# PCB_schematic.net
KiCad netlist of a schematic drawn in Altium Designer
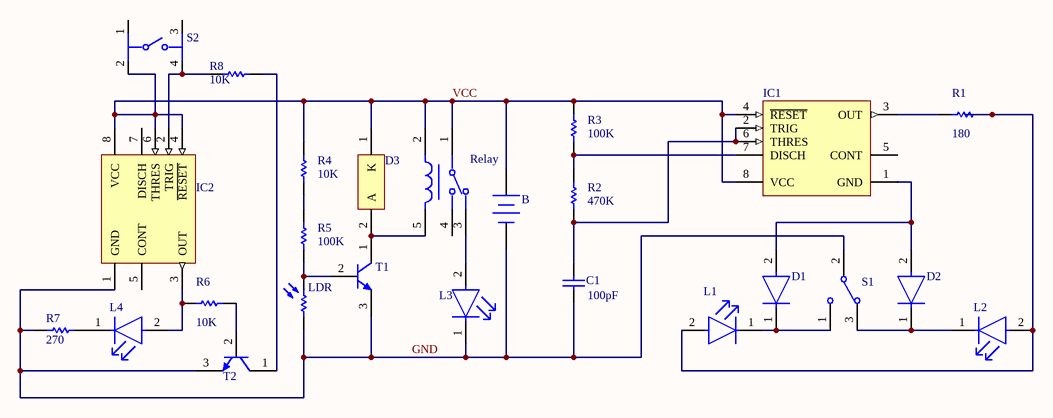
[diagram p0: PCB_schematic.SchDoc]

(export (version "E")
  (design (tool "Eeschema 10.0.6"))
  (components
    (comp (ref "B")
      (value "Battery")
      (footprint "BAT-2")
      (description "Multicell Battery")
      (fields (field (name "PUBLISHER") "Altium Limited"))
      (libsource (lib "Miscellaneous Devices") (part "Battery"))
    )
    (comp (ref "C1")
      (value "100pF")
      (footprint "RAD-0.3")
      (description "Capacitor")
      (fields (field (name "Comment") "Cap") (field (name "PUBLISHER") "Altium Limited"))
      (libsource (lib "Miscellaneous Devices") (part "Cap"))
    )
    (comp (ref "D1")
      (value "1N4007-E3/54")
      (footprint "FP-1N4007-MFG")
      (description "DIODE GEN PURP 1KV 1A DO204AL")
      (fields
        (field (name "OCTOPART") "https://octopart.com/1n4007-e3%2F54-vishay-39548207")
        (field (name "MANUFACTURER") "Vishay")
      )
      (libsource (lib "Altium Content Vault") (part "d7152d700b627762746794eb795d46e"))
    )
    (comp (ref "D2")
      (value "1N4007-E3/54")
      (footprint "FP-1N4007-MFG")
      (description "DIODE GEN PURP 1KV 1A DO204AL")
      (fields
        (field (name "OCTOPART") "https://octopart.com/1n4007-e3%2F54-vishay-39548207")
        (field (name "MANUFACTURER") "Vishay")
      )
      (libsource (lib "Altium Content Vault") (part "d7152d700b627762746794eb795d46e"))
    )
    (comp (ref "D3")
      (value "1N4001")
      (footprint "ONSC-AXIAL_LEAD-2-59-10_P")
      (description "Standard Recovery Rectifier, 2-Pin Axial_Lead, Pb-Free, Bulk Bag")
      (fields (field (name "MANUFACTURER") "On Semiconductor"))
      (libsource (lib "Altium Content Vault") (part "ONSC-D-K1A2-2_A"))
    )
    (comp (ref "IC1")
      (value "NE555P")
      (footprint "P0008A")
      (description "Precision Timer, 4.5 to 16 V, 0 to 70 degC, 8-Pin DIP, Pb-Free, Tube")
      (fields (field (name "MANUFACTURER") "TexasInstruments"))
      (libsource (lib "") (part "TI-NE555-P8_1"))
    )
    (comp (ref "IC2")
      (value "NE555P")
      (footprint "P0008A")
      (description "Precision Timer, 4.5 to 16 V, 0 to 70 degC, 8-Pin DIP, Pb-Free, Tube")
      (fields (field (name "MANUFACTURER") "TexasInstruments"))
      (libsource (lib "Altium Content Vault") (part "TI-NE555-P8"))
    )
    (comp (ref "L1")
      (value "HLMP-1719")
      (footprint "FP-HLMP-1719-MFG")
      (description "LED Uni-Color Yellow 2-Pin T-1")
      (fields (field (name "MANUFACTURER") "Broadcom"))
      (libsource (lib "Altium Content Vault") (part "8706943c75ba83719d021d2fdc84c58"))
    )
    (comp (ref "L2")
      (value "HLMP-1719")
      (footprint "FP-HLMP-1719-MFG")
      (description "LED Uni-Color Yellow 2-Pin T-1")
      (fields (field (name "MANUFACTURER") "Broadcom"))
      (libsource (lib "Altium Content Vault") (part "8706943c75ba83719d021d2fdc84c58"))
    )
    (comp (ref "L3")
      (value "HLMP-1719")
      (footprint "FP-HLMP-1719-MFG")
      (description "LED Uni-Color Yellow 2-Pin T-1")
      (fields (field (name "MANUFACTURER") "Broadcom"))
      (libsource (lib "Altium Content Vault") (part "8706943c75ba83719d021d2fdc84c58"))
    )
    (comp (ref "L4")
      (value "HLMP-1719")
      (footprint "FP-HLMP-1719-MFG")
      (description "LED Uni-Color Yellow 2-Pin T-1")
      (fields (field (name "MANUFACTURER") "Broadcom"))
      (libsource (lib "Altium Content Vault") (part "8706943c75ba83719d021d2fdc84c58"))
    )
    (comp (ref "LDR")
      (value "VT90N1")
      (footprint "EXCE-VT90N1")
      (description "Photoconductive Resistor, 200 kOhm, 100 V, 80 mW, -40 to 75 degC, 2-Pin THD, RoHS")
      (fields (field (name "MANUFACTURER") "Excelitas Technology"))
      (libsource (lib "Altium Content Vault") (part "PHOTO-RES-2"))
    )
    (comp (ref "R1")
      (value "180")
      (footprint "AXIAL-0.3")
      (description "Resistor")
      (fields (field (name "Comment") "Res1") (field (name "PUBLISHER") "Altium Limited"))
      (libsource (lib "Miscellaneous Devices") (part "Res1"))
    )
    (comp (ref "R2")
      (value "470K")
      (footprint "AXIAL-0.3")
      (description "Resistor")
      (fields (field (name "Comment") "Res1") (field (name "PUBLISHER") "Altium Limited"))
      (libsource (lib "Miscellaneous Devices") (part "Res1"))
    )
    (comp (ref "R3")
      (value "100K")
      (footprint "AXIAL-0.3")
      (description "Resistor")
      (fields (field (name "Comment") "Res1") (field (name "PUBLISHER") "Altium Limited"))
      (libsource (lib "Miscellaneous Devices") (part "Res1"))
    )
    (comp (ref "R4")
      (value "10K")
      (footprint "AXIAL-0.3")
      (description "Resistor")
      (fields (field (name "Comment") "Res1") (field (name "PUBLISHER") "Altium Limited"))
      (libsource (lib "Miscellaneous Devices") (part "Res1"))
    )
    (comp (ref "R5")
      (value "100K")
      (footprint "AXIAL-0.3")
      (description "Resistor")
      (fields (field (name "Comment") "Res1") (field (name "PUBLISHER") "Altium Limited"))
      (libsource (lib "Miscellaneous Devices") (part "Res1"))
    )
    (comp (ref "R6")
      (value "10K")
      (footprint "AXIAL-0.3")
      (description "Resistor")
      (fields (field (name "Comment") "Res1") (field (name "PUBLISHER") "Altium Limited"))
      (libsource (lib "Miscellaneous Devices") (part "Res1"))
    )
    (comp (ref "R7")
      (value "270")
      (footprint "AXIAL-0.3")
      (description "Resistor")
      (fields (field (name "Comment") "Res1") (field (name "PUBLISHER") "Altium Limited"))
      (libsource (lib "Miscellaneous Devices") (part "Res1"))
    )
    (comp (ref "R8")
      (value "10K")
      (footprint "AXIAL-0.3")
      (description "Resistor")
      (fields (field (name "Comment") "Res1") (field (name "PUBLISHER") "Altium Limited"))
      (libsource (lib "Miscellaneous Devices") (part "Res1"))
    )
    (comp (ref "Relay")
      (value "JS1F-12V-F")
      (footprint "FP-JS1F-12V-F-MFG")
      (description "RELAY GEN PURPOSE SPDT 10A 12V")
      (libsource (lib "Altium Content Vault") (part "ff81c261b07bbb1a4e05c84e23c1c37"))
    )
    (comp (ref "S1")
      (value "SW-SPDT")
      (footprint "TL36WW15050")
      (description "SPDT Subminiature Toggle Switch, Right Angle Mounting, Vertical Actuation")
      (fields (field (name "PUBLISHER") "Altium Limited"))
      (libsource (lib "Miscellaneous Devices") (part "SW-SPDT"))
    )
    (comp (ref "S2")
      (value "3-1825910-1")
      (footprint "FP-3-1825910-1-MFG")
      (description "SWITCH TACTILE SPST-NO 0.05A 24V")
      (fields
        (field (name "MANUFACTURER") "TE Connectivity")
        (field (name "OCTOPART") "https://octopart.com/3-1825910-1-te+connectivity-46506874")
      )
      (libsource (lib "Altium Content Vault") (part "b8895f3f4cefb76e1819d2863dba89b"))
    )
    (comp (ref "T1")
      (value "BC547B")
      (footprint "ONSC-TO-92-3-29-11")
      (description "Amplifier Transistor, NPN Silicon, 3-Pin TO-92, Bulk Box")
      (fields (field (name "MANUFACTURER") "On Semiconductor"))
      (libsource (lib "Altium Content Vault") (part "ONSC-NPN-C1B2E3-3"))
    )
    (comp (ref "T2")
      (value "BC547B")
      (footprint "ONSC-TO-92-3-29-11")
      (description "Amplifier Transistor, NPN Silicon, 3-Pin TO-92, Bulk Box")
      (fields (field (name "MANUFACTURER") "On Semiconductor"))
      (libsource (lib "Altium Content Vault") (part "ONSC-NPN-C1B2E3-3"))
    )
  )
  (nets
    (net (code "1") (name "/GND") (class "Default")
      (node (ref "B") (pin "2") (pinfunction "-_2") (pintype "passive"))
      (node (ref "C1") (pin "1") (pinfunction "1_1") (pintype "passive"))
      (node (ref "IC2") (pin "1") (pinfunction "GND_1") (pintype "power_in"))
      (node (ref "L3") (pin "1") (pinfunction "C_1") (pintype "passive"))
      (node (ref "LDR") (pin "1") (pinfunction "1_1") (pintype "passive"))
      (node (ref "R7") (pin "1") (pinfunction "1_1") (pintype "passive"))
      (node (ref "S1") (pin "2") (pinfunction "2_2") (pintype "passive"))
      (node (ref "T1") (pin "3") (pinfunction "E_3") (pintype "passive"))
      (node (ref "T2") (pin "3") (pinfunction "E_3") (pintype "passive"))
    )
    (net (code "2") (name "/VCC") (class "Default")
      (node (ref "B") (pin "1") (pinfunction "+_1") (pintype "passive"))
      (node (ref "D3") (pin "1") (pinfunction "K_1") (pintype "passive"))
      (node (ref "IC1") (pin "4") (pinfunction "~{RESET}_4") (pintype "input"))
      (node (ref "IC1") (pin "8") (pinfunction "VCC_8") (pintype "power_in"))
      (node (ref "IC2") (pin "4") (pinfunction "~{RESET}_4") (pintype "input"))
      (node (ref "IC2") (pin "6") (pinfunction "THRES_6") (pintype "input"))
      (node (ref "IC2") (pin "8") (pinfunction "VCC_8") (pintype "power_in"))
      (node (ref "R3") (pin "2") (pinfunction "2_2") (pintype "passive"))
      (node (ref "R4") (pin "2") (pinfunction "2_2") (pintype "passive"))
      (node (ref "Relay") (pin "1") (pinfunction "COM_1") (pintype "passive"))
      (node (ref "Relay") (pin "2") (pinfunction "2_2") (pintype "passive"))
      (node (ref "S2") (pin "2") (pinfunction "2_2") (pintype "passive"))
    )
    (net (code "3") (name "Net-(D1-A)") (class "Default")
      (node (ref "D1") (pin "2") (pinfunction "A_2") (pintype "passive"))
      (node (ref "D2") (pin "2") (pinfunction "A_2") (pintype "passive"))
      (node (ref "IC1") (pin "1") (pinfunction "GND_1") (pintype "power_in"))
    )
    (net (code "4") (name "Net-(D1-C)") (class "Default")
      (node (ref "D1") (pin "1") (pinfunction "C_1") (pintype "passive"))
      (node (ref "L1") (pin "1") (pinfunction "C_1") (pintype "passive"))
      (node (ref "S1") (pin "1") (pinfunction "1_1") (pintype "passive"))
    )
    (net (code "5") (name "Net-(D2-C)") (class "Default")
      (node (ref "D2") (pin "1") (pinfunction "C_1") (pintype "passive"))
      (node (ref "L2") (pin "1") (pinfunction "C_1") (pintype "passive"))
      (node (ref "S1") (pin "3") (pinfunction "3_3") (pintype "passive"))
    )
    (net (code "6") (name "Net-(D3-A)") (class "Default")
      (node (ref "D3") (pin "2") (pinfunction "A_2") (pintype "passive"))
      (node (ref "Relay") (pin "5") (pinfunction "5_5") (pintype "passive"))
      (node (ref "T1") (pin "1") (pinfunction "C_1") (pintype "passive"))
    )
    (net (code "7") (name "Net-(IC1-DISCH)") (class "Default")
      (node (ref "IC1") (pin "7") (pinfunction "DISCH_7") (pintype "open_collector"))
      (node (ref "R2") (pin "2") (pinfunction "2_2") (pintype "passive"))
      (node (ref "R3") (pin "1") (pinfunction "1_1") (pintype "passive"))
    )
    (net (code "8") (name "Net-(IC1-OUT)") (class "Default")
      (node (ref "IC1") (pin "3") (pinfunction "OUT_3") (pintype "output"))
      (node (ref "R1") (pin "2") (pinfunction "2_2") (pintype "passive"))
    )
    (net (code "9") (name "Net-(IC1-THRES)") (class "Default")
      (node (ref "C1") (pin "2") (pinfunction "2_2") (pintype "passive"))
      (node (ref "IC1") (pin "2") (pinfunction "TRIG_2") (pintype "input"))
      (node (ref "IC1") (pin "6") (pinfunction "THRES_6") (pintype "input"))
      (node (ref "R2") (pin "1") (pinfunction "1_1") (pintype "passive"))
    )
    (net (code "10") (name "Net-(IC2-OUT)") (class "Default")
      (node (ref "IC2") (pin "3") (pinfunction "OUT_3") (pintype "output"))
      (node (ref "L4") (pin "2") (pinfunction "A_2") (pintype "passive"))
      (node (ref "R6") (pin "1") (pinfunction "1_1") (pintype "passive"))
    )
    (net (code "11") (name "Net-(IC2-TRIG)") (class "Default")
      (node (ref "IC2") (pin "2") (pinfunction "TRIG_2") (pintype "input"))
      (node (ref "R8") (pin "1") (pinfunction "1_1") (pintype "passive"))
      (node (ref "S2") (pin "4") (pinfunction "4_4") (pintype "passive"))
    )
    (net (code "12") (name "Net-(L1-A)") (class "Default")
      (node (ref "L1") (pin "2") (pinfunction "A_2") (pintype "passive"))
      (node (ref "L2") (pin "2") (pinfunction "A_2") (pintype "passive"))
      (node (ref "R1") (pin "1") (pinfunction "1_1") (pintype "passive"))
    )
    (net (code "13") (name "Net-(L3-A)") (class "Default")
      (node (ref "L3") (pin "2") (pinfunction "A_2") (pintype "passive"))
      (node (ref "Relay") (pin "3") (pinfunction "NO_3") (pintype "passive"))
    )
    (net (code "14") (name "Net-(L4-C)") (class "Default")
      (node (ref "L4") (pin "1") (pinfunction "C_1") (pintype "passive"))
      (node (ref "R7") (pin "2") (pinfunction "2_2") (pintype "passive"))
    )
    (net (code "15") (name "Net-(R4-Pad1)") (class "Default")
      (node (ref "R4") (pin "1") (pinfunction "1_1") (pintype "passive"))
      (node (ref "R5") (pin "2") (pinfunction "2_2") (pintype "passive"))
    )
    (net (code "16") (name "Net-(T1-B)") (class "Default")
      (node (ref "LDR") (pin "2") (pinfunction "2_2") (pintype "passive"))
      (node (ref "R5") (pin "1") (pinfunction "1_1") (pintype "passive"))
      (node (ref "T1") (pin "2") (pinfunction "B_2") (pintype "passive"))
    )
    (net (code "17") (name "Net-(T2-B)") (class "Default")
      (node (ref "R6") (pin "2") (pinfunction "2_2") (pintype "passive"))
      (node (ref "T2") (pin "2") (pinfunction "B_2") (pintype "passive"))
    )
    (net (code "18") (name "Net-(T2-C)") (class "Default")
      (node (ref "R8") (pin "2") (pinfunction "2_2") (pintype "passive"))
      (node (ref "T2") (pin "1") (pinfunction "C_1") (pintype "passive"))
    )
    (net (code "19") (name "unconnected-(IC1-CONT-Pad5)") (class "Default")
      (node (ref "IC1") (pin "5") (pinfunction "CONT_5") (pintype "passive"))
    )
    (net (code "20") (name "unconnected-(IC2-CONT-Pad5)") (class "Default")
      (node (ref "IC2") (pin "5") (pinfunction "CONT_5") (pintype "passive"))
    )
    (net (code "21") (name "unconnected-(IC2-DISCH-Pad7)") (class "Default")
      (node (ref "IC2") (pin "7") (pinfunction "DISCH_7") (pintype "open_collector"))
    )
    (net (code "22") (name "unconnected-(Relay-NC-Pad4)") (class "Default")
      (node (ref "Relay") (pin "4") (pinfunction "NC_4") (pintype "passive"))
    )
    (net (code "23") (name "unconnected-(S2-Pad1)") (class "Default")
      (node (ref "S2") (pin "1") (pinfunction "1_1") (pintype "passive"))
    )
    (net (code "24") (name "unconnected-(S2-Pad3)") (class "Default")
      (node (ref "S2") (pin "3") (pinfunction "3_3") (pintype "passive"))
    )
  )
)
